# LCD.net
KiCad netlist of a schematic drawn in Altium Designer
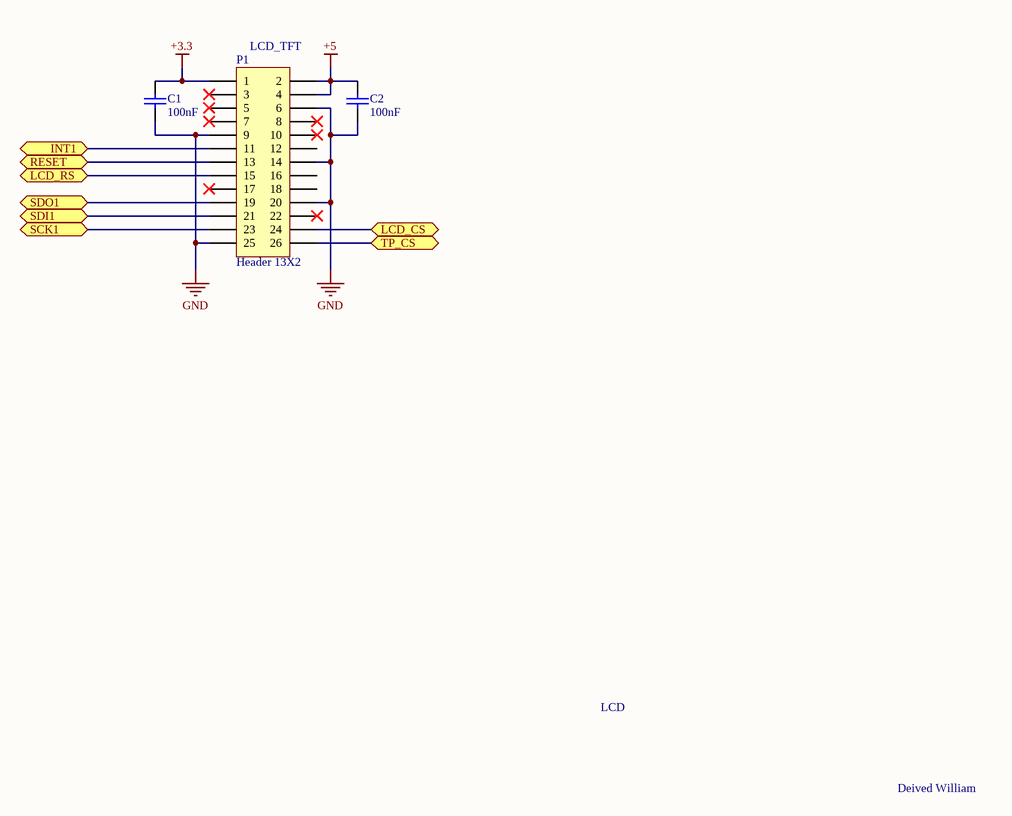
[diagram p0: LCD.SchDoc]

(export (version "E")
  (design (tool "Eeschema 10.0.6"))
  (components
    (comp (ref "C1")
      (value "100nF")
      (footprint "WCAP-CSGP_0603, 1.6x0.8x0.8mm_Reflow")
      (description "WCAP-CSGP Ceramic Capacitors, size 0603, 1.6x0.8x0.8mm, 10V, X7R, 100nF")
      (fields (field (name "PART NUMBER") "885012206020") (field (name "PUBLISHER") "Wurth Elektronik"))
      (libsource (lib "Altium_WCAP-CSGP (rev17a)") (part "885012206020"))
    )
    (comp (ref "C2")
      (value "100nF")
      (footprint "WCAP-CSGP_0603, 1.6x0.8x0.8mm_Reflow")
      (description "WCAP-CSGP Ceramic Capacitors, size 0603, 1.6x0.8x0.8mm, 10V, X7R, 100nF")
      (fields (field (name "PART NUMBER") "885012206020") (field (name "PUBLISHER") "Wurth Elektronik"))
      (libsource (lib "Altium_WCAP-CSGP (rev17a)") (part "885012206020"))
    )
    (comp (ref "P1")
      (value "Header 13X2")
      (footprint "HDR2X13")
      (description "Header, 13-Pin, Dual row")
      (fields (field (name "PUBLISHER") "Altium Limited"))
      (libsource (lib "Miscellaneous Connectors") (part "Header 13X2"))
    )
  )
  (nets
    (net (code "1") (name "+3.3") (class "Default")
      (node (ref "C1") (pin "2") (pinfunction "2_2") (pintype "passive"))
      (node (ref "P1") (pin "1") (pinfunction "1_1") (pintype "passive"))
    )
    (net (code "2") (name "+5") (class "Default")
      (node (ref "C2") (pin "2") (pinfunction "2_2") (pintype "passive"))
      (node (ref "P1") (pin "2") (pinfunction "2_2") (pintype "passive"))
      (node (ref "P1") (pin "4") (pinfunction "4_4") (pintype "passive"))
    )
    (net (code "3") (name "/INT1") (class "Default")
      (node (ref "P1") (pin "11") (pinfunction "11_11") (pintype "passive"))
    )
    (net (code "4") (name "/LCD_CS") (class "Default")
      (node (ref "P1") (pin "24") (pinfunction "24_24") (pintype "passive"))
    )
    (net (code "5") (name "/LCD_RS") (class "Default")
      (node (ref "P1") (pin "15") (pinfunction "15_15") (pintype "passive"))
    )
    (net (code "6") (name "/RESET") (class "Default")
      (node (ref "P1") (pin "13") (pinfunction "13_13") (pintype "passive"))
    )
    (net (code "7") (name "/SCK1") (class "Default")
      (node (ref "P1") (pin "23") (pinfunction "23_23") (pintype "passive"))
    )
    (net (code "8") (name "/SDI1") (class "Default")
      (node (ref "P1") (pin "21") (pinfunction "21_21") (pintype "passive"))
    )
    (net (code "9") (name "/SDO1") (class "Default")
      (node (ref "P1") (pin "19") (pinfunction "19_19") (pintype "passive"))
    )
    (net (code "10") (name "/TP_CS") (class "Default")
      (node (ref "P1") (pin "26") (pinfunction "26_26") (pintype "passive"))
    )
    (net (code "11") (name "GND") (class "Default")
      (node (ref "C1") (pin "1") (pinfunction "1_1") (pintype "passive"))
      (node (ref "C2") (pin "1") (pinfunction "1_1") (pintype "passive"))
      (node (ref "P1") (pin "14") (pinfunction "14_14") (pintype "passive"))
      (node (ref "P1") (pin "20") (pinfunction "20_20") (pintype "passive"))
      (node (ref "P1") (pin "25") (pinfunction "25_25") (pintype "passive"))
      (node (ref "P1") (pin "6") (pinfunction "6_6") (pintype "passive"))
      (node (ref "P1") (pin "9") (pinfunction "9_9") (pintype "passive"))
    )
    (net (code "12") (name "unconnected-(P1-Pad3)") (class "Default")
      (node (ref "P1") (pin "3") (pinfunction "3_3") (pintype "passive+no_connect"))
    )
    (net (code "13") (name "unconnected-(P1-Pad5)") (class "Default")
      (node (ref "P1") (pin "5") (pinfunction "5_5") (pintype "passive+no_connect"))
    )
    (net (code "14") (name "unconnected-(P1-Pad7)") (class "Default")
      (node (ref "P1") (pin "7") (pinfunction "7_7") (pintype "passive+no_connect"))
    )
    (net (code "15") (name "unconnected-(P1-Pad8)") (class "Default")
      (node (ref "P1") (pin "8") (pinfunction "8_8") (pintype "passive+no_connect"))
    )
    (net (code "16") (name "unconnected-(P1-Pad10)") (class "Default")
      (node (ref "P1") (pin "10") (pinfunction "10_10") (pintype "passive+no_connect"))
    )
    (net (code "17") (name "unconnected-(P1-Pad12)") (class "Default")
      (node (ref "P1") (pin "12") (pinfunction "12_12") (pintype "passive"))
    )
    (net (code "18") (name "unconnected-(P1-Pad16)") (class "Default")
      (node (ref "P1") (pin "16") (pinfunction "16_16") (pintype "passive"))
    )
    (net (code "19") (name "unconnected-(P1-Pad17)") (class "Default")
      (node (ref "P1") (pin "17") (pinfunction "17_17") (pintype "passive+no_connect"))
    )
    (net (code "20") (name "unconnected-(P1-Pad18)") (class "Default")
      (node (ref "P1") (pin "18") (pinfunction "18_18") (pintype "passive"))
    )
    (net (code "21") (name "unconnected-(P1-Pad22)") (class "Default")
      (node (ref "P1") (pin "22") (pinfunction "22_22") (pintype "passive+no_connect"))
    )
  )
)
